# 001.net
KiCad netlist of a schematic drawn in EAGLE
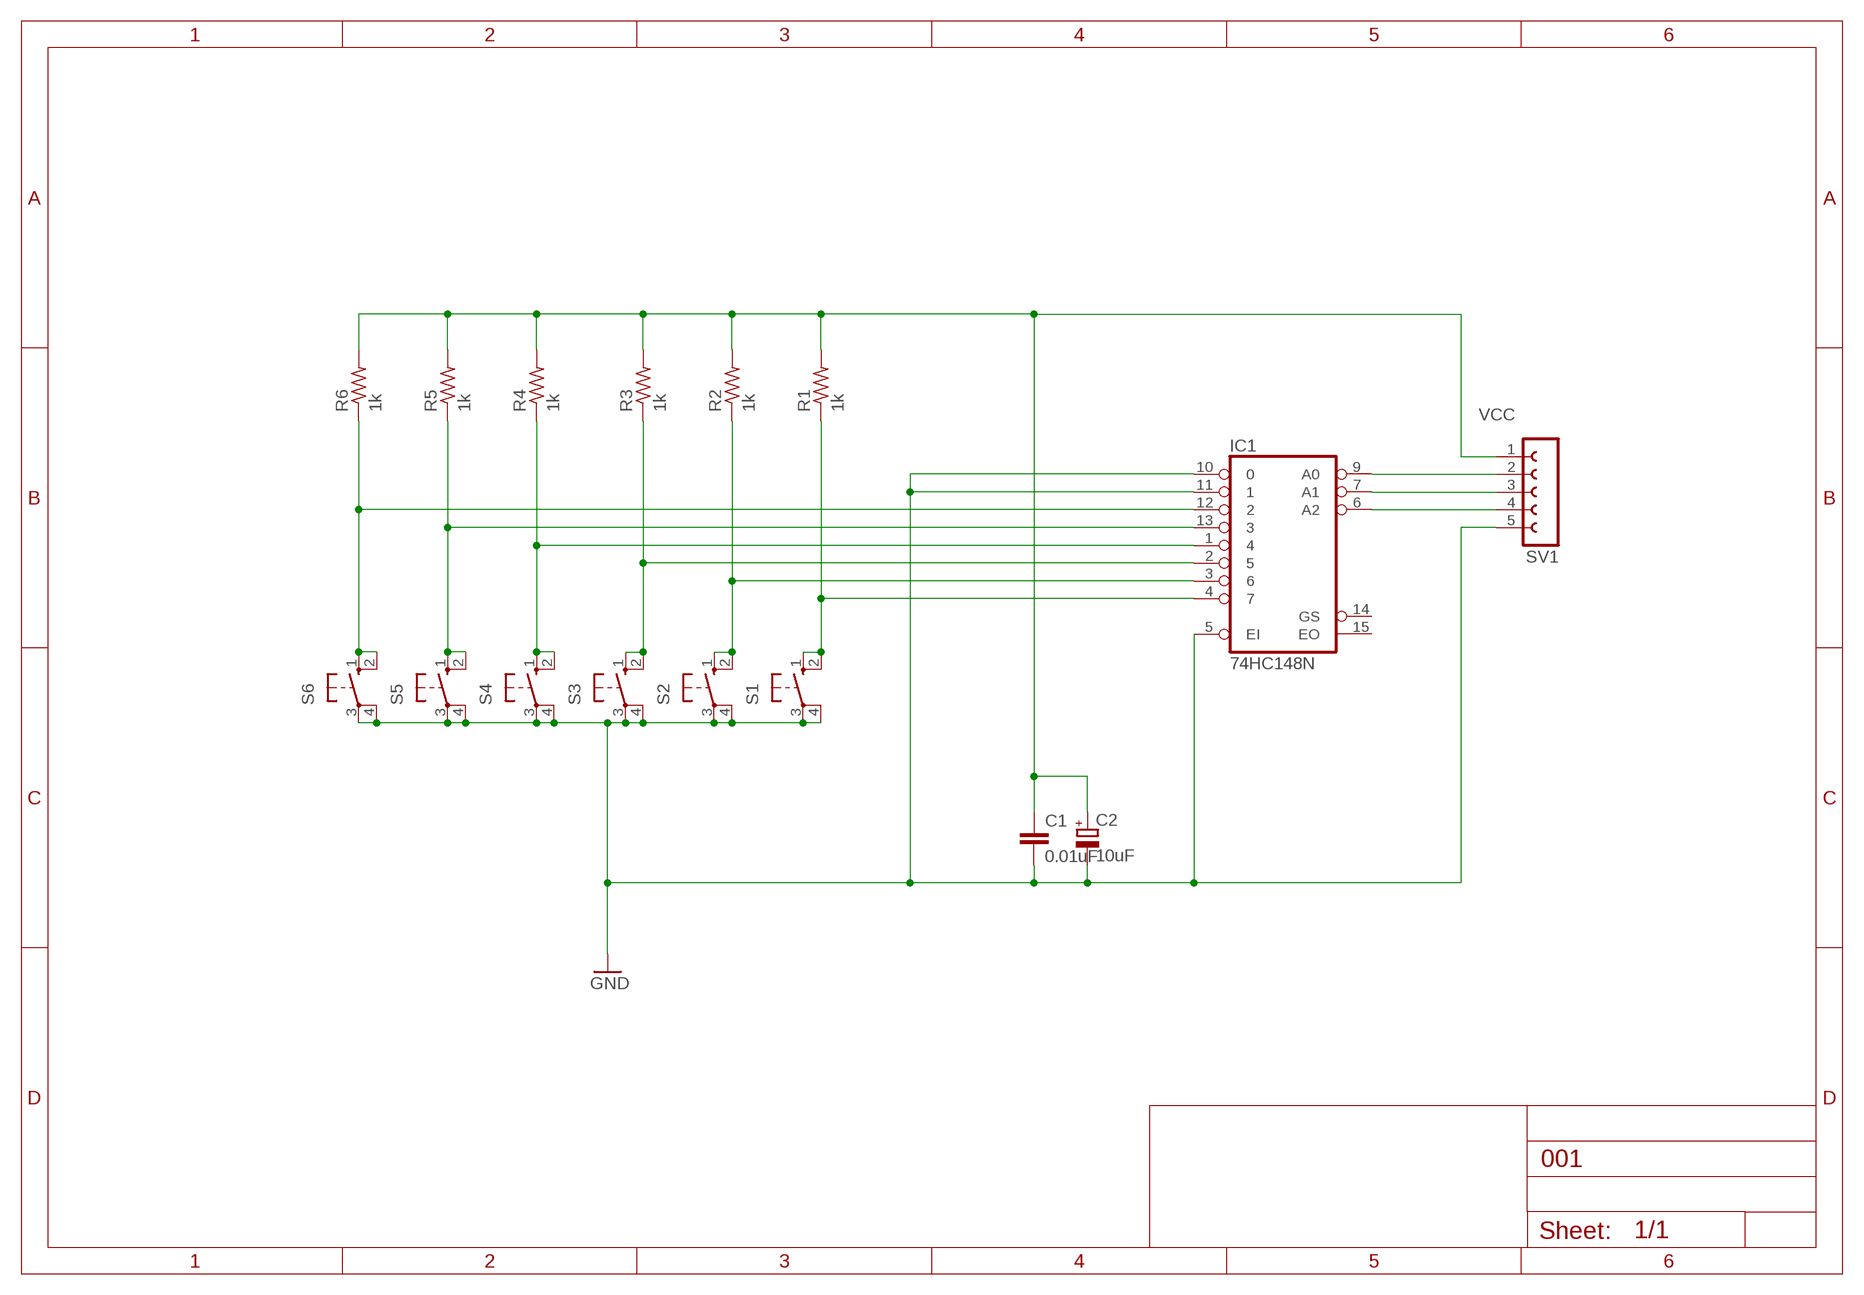
[diagram p0: schematic, sheet 1]

(export (version "E")
  (design (tool "Eeschema 10.0.6"))
  (components
    (comp (ref "C1")
      (value "0.01uF")
      (footprint "eagle-import:C025-025X050")
      (libsource (lib "eagle-import") (part "C-EU025-025X050"))
    )
    (comp (ref "C2")
      (value "10uF")
      (footprint "eagle-import:E2,5-6E")
      (libsource (lib "eagle-import") (part "CPOL-EUE2,5-6E"))
    )
    (comp (ref "IC1")
      (value "74HC148N")
      (footprint "eagle-import:DIL16")
      (libsource (lib "eagle-import") (part "74148NHC"))
    )
    (comp (ref "R1")
      (value "1k")
      (footprint "eagle-import:0207_7")
      (libsource (lib "eagle-import") (part "R-US_0207/7"))
    )
    (comp (ref "R2")
      (value "1k")
      (footprint "eagle-import:0207_7")
      (libsource (lib "eagle-import") (part "R-US_0207/7"))
    )
    (comp (ref "R3")
      (value "1k")
      (footprint "eagle-import:0207_7")
      (libsource (lib "eagle-import") (part "R-US_0207/7"))
    )
    (comp (ref "R4")
      (value "1k")
      (footprint "eagle-import:0207_7")
      (libsource (lib "eagle-import") (part "R-US_0207/7"))
    )
    (comp (ref "R5")
      (value "1k")
      (footprint "eagle-import:0207_7")
      (libsource (lib "eagle-import") (part "R-US_0207/7"))
    )
    (comp (ref "R6")
      (value "1k")
      (footprint "eagle-import:0207_7")
      (libsource (lib "eagle-import") (part "R-US_0207/7"))
    )
    (comp (ref "S1")
      (value "10-XX")
      (footprint "eagle-import:B3F-10XX")
      (libsource (lib "eagle-import") (part "10-XX"))
    )
    (comp (ref "S2")
      (value "10-XX")
      (footprint "eagle-import:B3F-10XX")
      (libsource (lib "eagle-import") (part "10-XX"))
    )
    (comp (ref "S3")
      (value "10-XX")
      (footprint "eagle-import:B3F-10XX")
      (libsource (lib "eagle-import") (part "10-XX"))
    )
    (comp (ref "S4")
      (value "10-XX")
      (footprint "eagle-import:B3F-10XX")
      (libsource (lib "eagle-import") (part "10-XX"))
    )
    (comp (ref "S5")
      (value "10-XX")
      (footprint "eagle-import:B3F-10XX")
      (libsource (lib "eagle-import") (part "10-XX"))
    )
    (comp (ref "S6")
      (value "10-XX")
      (footprint "eagle-import:B3F-10XX")
      (libsource (lib "eagle-import") (part "10-XX"))
    )
    (comp (ref "SV1")
      (value "FE05-1")
      (footprint "eagle-import:FE05-1")
      (libsource (lib "eagle-import") (part "FE05-1"))
    )
  )
  (nets
    (net (code "1") (name "/VCC") (class "Default")
      (node (ref "C1") (pin "1") (pinfunction "1_1") (pintype "passive"))
      (node (ref "C2") (pin "+") (pinfunction "+_+") (pintype "passive"))
      (node (ref "R1") (pin "2") (pinfunction "2_2") (pintype "passive"))
      (node (ref "R2") (pin "2") (pinfunction "2_2") (pintype "passive"))
      (node (ref "R3") (pin "2") (pinfunction "2_2") (pintype "passive"))
      (node (ref "R4") (pin "2") (pinfunction "2_2") (pintype "passive"))
      (node (ref "R5") (pin "2") (pinfunction "2_2") (pintype "passive"))
      (node (ref "R6") (pin "2") (pinfunction "2_2") (pintype "passive"))
      (node (ref "SV1") (pin "1") (pinfunction "1_1") (pintype "passive"))
    )
    (net (code "2") (name "GND") (class "Default")
      (node (ref "C1") (pin "2") (pinfunction "2_2") (pintype "passive"))
      (node (ref "C2") (pin "-") (pinfunction "-_-") (pintype "passive"))
      (node (ref "IC1") (pin "10") (pinfunction "0_10") (pintype "input"))
      (node (ref "IC1") (pin "11") (pinfunction "1_11") (pintype "input"))
      (node (ref "IC1") (pin "5") (pinfunction "EI_5") (pintype "input"))
      (node (ref "S1") (pin "3") (pinfunction "P_3") (pintype "passive"))
      (node (ref "S1") (pin "4") (pinfunction "P1_4") (pintype "passive"))
      (node (ref "S2") (pin "3") (pinfunction "P_3") (pintype "passive"))
      (node (ref "S2") (pin "4") (pinfunction "P1_4") (pintype "passive"))
      (node (ref "S3") (pin "3") (pinfunction "P_3") (pintype "passive"))
      (node (ref "S3") (pin "4") (pinfunction "P1_4") (pintype "passive"))
      (node (ref "S4") (pin "3") (pinfunction "P_3") (pintype "passive"))
      (node (ref "S4") (pin "4") (pinfunction "P1_4") (pintype "passive"))
      (node (ref "S5") (pin "3") (pinfunction "P_3") (pintype "passive"))
      (node (ref "S5") (pin "4") (pinfunction "P1_4") (pintype "passive"))
      (node (ref "S6") (pin "3") (pinfunction "P_3") (pintype "passive"))
      (node (ref "S6") (pin "4") (pinfunction "P1_4") (pintype "passive"))
      (node (ref "SV1") (pin "5") (pinfunction "5_5") (pintype "passive"))
    )
    (net (code "3") (name "Net-(IC1A-2)") (class "Default")
      (node (ref "IC1") (pin "12") (pinfunction "2_12") (pintype "input"))
      (node (ref "R6") (pin "1") (pinfunction "1_1") (pintype "passive"))
      (node (ref "S6") (pin "1") (pinfunction "S_1") (pintype "passive"))
      (node (ref "S6") (pin "2") (pinfunction "S1_2") (pintype "passive"))
    )
    (net (code "4") (name "Net-(IC1A-3)") (class "Default")
      (node (ref "IC1") (pin "13") (pinfunction "3_13") (pintype "input"))
      (node (ref "R5") (pin "1") (pinfunction "1_1") (pintype "passive"))
      (node (ref "S5") (pin "1") (pinfunction "S_1") (pintype "passive"))
      (node (ref "S5") (pin "2") (pinfunction "S1_2") (pintype "passive"))
    )
    (net (code "5") (name "Net-(IC1A-4)") (class "Default")
      (node (ref "IC1") (pin "1") (pinfunction "4_1") (pintype "input"))
      (node (ref "R4") (pin "1") (pinfunction "1_1") (pintype "passive"))
      (node (ref "S4") (pin "1") (pinfunction "S_1") (pintype "passive"))
      (node (ref "S4") (pin "2") (pinfunction "S1_2") (pintype "passive"))
    )
    (net (code "6") (name "Net-(IC1A-5)") (class "Default")
      (node (ref "IC1") (pin "2") (pinfunction "5_2") (pintype "input"))
      (node (ref "R3") (pin "1") (pinfunction "1_1") (pintype "passive"))
      (node (ref "S3") (pin "1") (pinfunction "S_1") (pintype "passive"))
      (node (ref "S3") (pin "2") (pinfunction "S1_2") (pintype "passive"))
    )
    (net (code "7") (name "Net-(IC1A-6)") (class "Default")
      (node (ref "IC1") (pin "3") (pinfunction "6_3") (pintype "input"))
      (node (ref "R2") (pin "1") (pinfunction "1_1") (pintype "passive"))
      (node (ref "S2") (pin "1") (pinfunction "S_1") (pintype "passive"))
      (node (ref "S2") (pin "2") (pinfunction "S1_2") (pintype "passive"))
    )
    (net (code "8") (name "Net-(IC1A-7)") (class "Default")
      (node (ref "IC1") (pin "4") (pinfunction "7_4") (pintype "input"))
      (node (ref "R1") (pin "1") (pinfunction "1_1") (pintype "passive"))
      (node (ref "S1") (pin "1") (pinfunction "S_1") (pintype "passive"))
      (node (ref "S1") (pin "2") (pinfunction "S1_2") (pintype "passive"))
    )
    (net (code "9") (name "Net-(IC1A-A0)") (class "Default")
      (node (ref "IC1") (pin "9") (pinfunction "A0_9") (pintype "output"))
      (node (ref "SV1") (pin "2") (pinfunction "2_2") (pintype "passive"))
    )
    (net (code "10") (name "Net-(IC1A-A1)") (class "Default")
      (node (ref "IC1") (pin "7") (pinfunction "A1_7") (pintype "output"))
      (node (ref "SV1") (pin "3") (pinfunction "3_3") (pintype "passive"))
    )
    (net (code "11") (name "Net-(IC1A-A2)") (class "Default")
      (node (ref "IC1") (pin "6") (pinfunction "A2_6") (pintype "output"))
      (node (ref "SV1") (pin "4") (pinfunction "4_4") (pintype "passive"))
    )
    (net (code "12") (name "unconnected-(IC1A-EO-Pad15)") (class "Default")
      (node (ref "IC1") (pin "15") (pinfunction "EO_15") (pintype "output"))
    )
    (net (code "13") (name "unconnected-(IC1A-GS-Pad14)") (class "Default")
      (node (ref "IC1") (pin "14") (pinfunction "GS_14") (pintype "output"))
    )
  )
)
